# IMU.net
KiCad netlist of a schematic drawn in Altium Designer
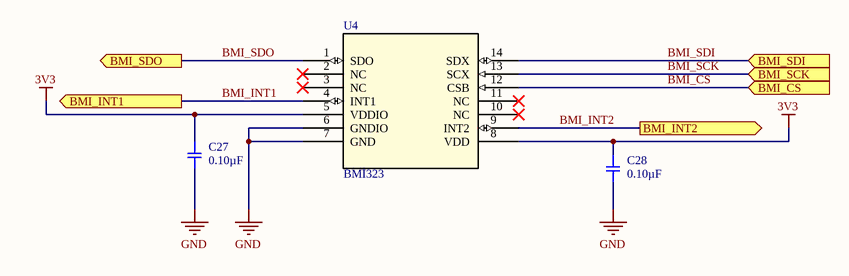
[diagram p0: IMU.SchDoc]

(export (version "E")
  (design (tool "Eeschema 10.0.6"))
  (components
    (comp (ref "C27")
      (value "0.10µF")
      (footprint "SMD-0402C")
      (description "CAP CER 0.1UF 10V X5R 0402")
      (fields (field (name "DIGI-KEY PART NUMBER") "490-6297-1-ND") (field (name "VOLTAGE") "10V"))
      (libsource (lib "University of British Columbia") (part "ZRB15XR61A475ME01D"))
    )
    (comp (ref "C28")
      (value "0.10µF")
      (footprint "SMD-0402C")
      (description "CAP CER 0.1UF 10V X5R 0402")
      (fields (field (name "DIGI-KEY PART NUMBER") "490-6297-1-ND") (field (name "VOLTAGE") "10V"))
      (libsource (lib "University of British Columbia") (part "ZRB15XR61A475ME01D"))
    )
    (comp (ref "U4")
      (value "BMI323")
      (footprint "BMI323_BOS")
      (description "Description")
      (fields (field (name "COPYRIGHT") "Copyright (C) 2025 Ultra Librarian. All rights reserved."))
      (libsource (lib "Jack Kelly") (part "BMI323"))
    )
  )
  (nets
    (net (code "1") (name "/BMI_CS") (class "Default")
      (node (ref "U4") (pin "12") (pinfunction "CSB_12") (pintype "input"))
    )
    (net (code "2") (name "/BMI_INT1") (class "Default")
      (node (ref "U4") (pin "4") (pinfunction "INT1_4") (pintype "bidirectional"))
    )
    (net (code "3") (name "/BMI_INT2") (class "Default")
      (node (ref "U4") (pin "9") (pinfunction "INT2_9") (pintype "bidirectional"))
    )
    (net (code "4") (name "/BMI_SCK") (class "Default")
      (node (ref "U4") (pin "13") (pinfunction "SCX_13") (pintype "input"))
    )
    (net (code "5") (name "/BMI_SDI") (class "Default")
      (node (ref "U4") (pin "14") (pinfunction "SDX_14") (pintype "bidirectional"))
    )
    (net (code "6") (name "/BMI_SDO") (class "Default")
      (node (ref "U4") (pin "1") (pinfunction "SDO_1") (pintype "bidirectional"))
    )
    (net (code "7") (name "3V3") (class "Default")
      (node (ref "C27") (pin "1") (pinfunction "1_1") (pintype "passive"))
      (node (ref "C28") (pin "1") (pinfunction "1_1") (pintype "passive"))
      (node (ref "U4") (pin "5") (pinfunction "VDDIO_5") (pintype "power_in"))
      (node (ref "U4") (pin "8") (pinfunction "VDD_8") (pintype "power_in"))
    )
    (net (code "8") (name "GND") (class "Default")
      (node (ref "C27") (pin "2") (pinfunction "2_2") (pintype "passive"))
      (node (ref "C28") (pin "2") (pinfunction "2_2") (pintype "passive"))
      (node (ref "U4") (pin "6") (pinfunction "GNDIO_6") (pintype "power_in"))
      (node (ref "U4") (pin "7") (pinfunction "GND_7") (pintype "power_in"))
    )
    (net (code "9") (name "unconnected-(U4-NC-Pad2)") (class "Default")
      (node (ref "U4") (pin "2") (pinfunction "NC_2") (pintype "passive+no_connect"))
    )
    (net (code "10") (name "unconnected-(U4-NC-Pad3)") (class "Default")
      (node (ref "U4") (pin "3") (pinfunction "NC_3") (pintype "passive+no_connect"))
    )
    (net (code "11") (name "unconnected-(U4-NC-Pad10)") (class "Default")
      (node (ref "U4") (pin "10") (pinfunction "NC_10") (pintype "passive+no_connect"))
    )
    (net (code "12") (name "unconnected-(U4-NC-Pad11)") (class "Default")
      (node (ref "U4") (pin "11") (pinfunction "NC_11") (pintype "passive+no_connect"))
    )
  )
)
